# controller.net
KiCad netlist of a schematic drawn in EAGLE
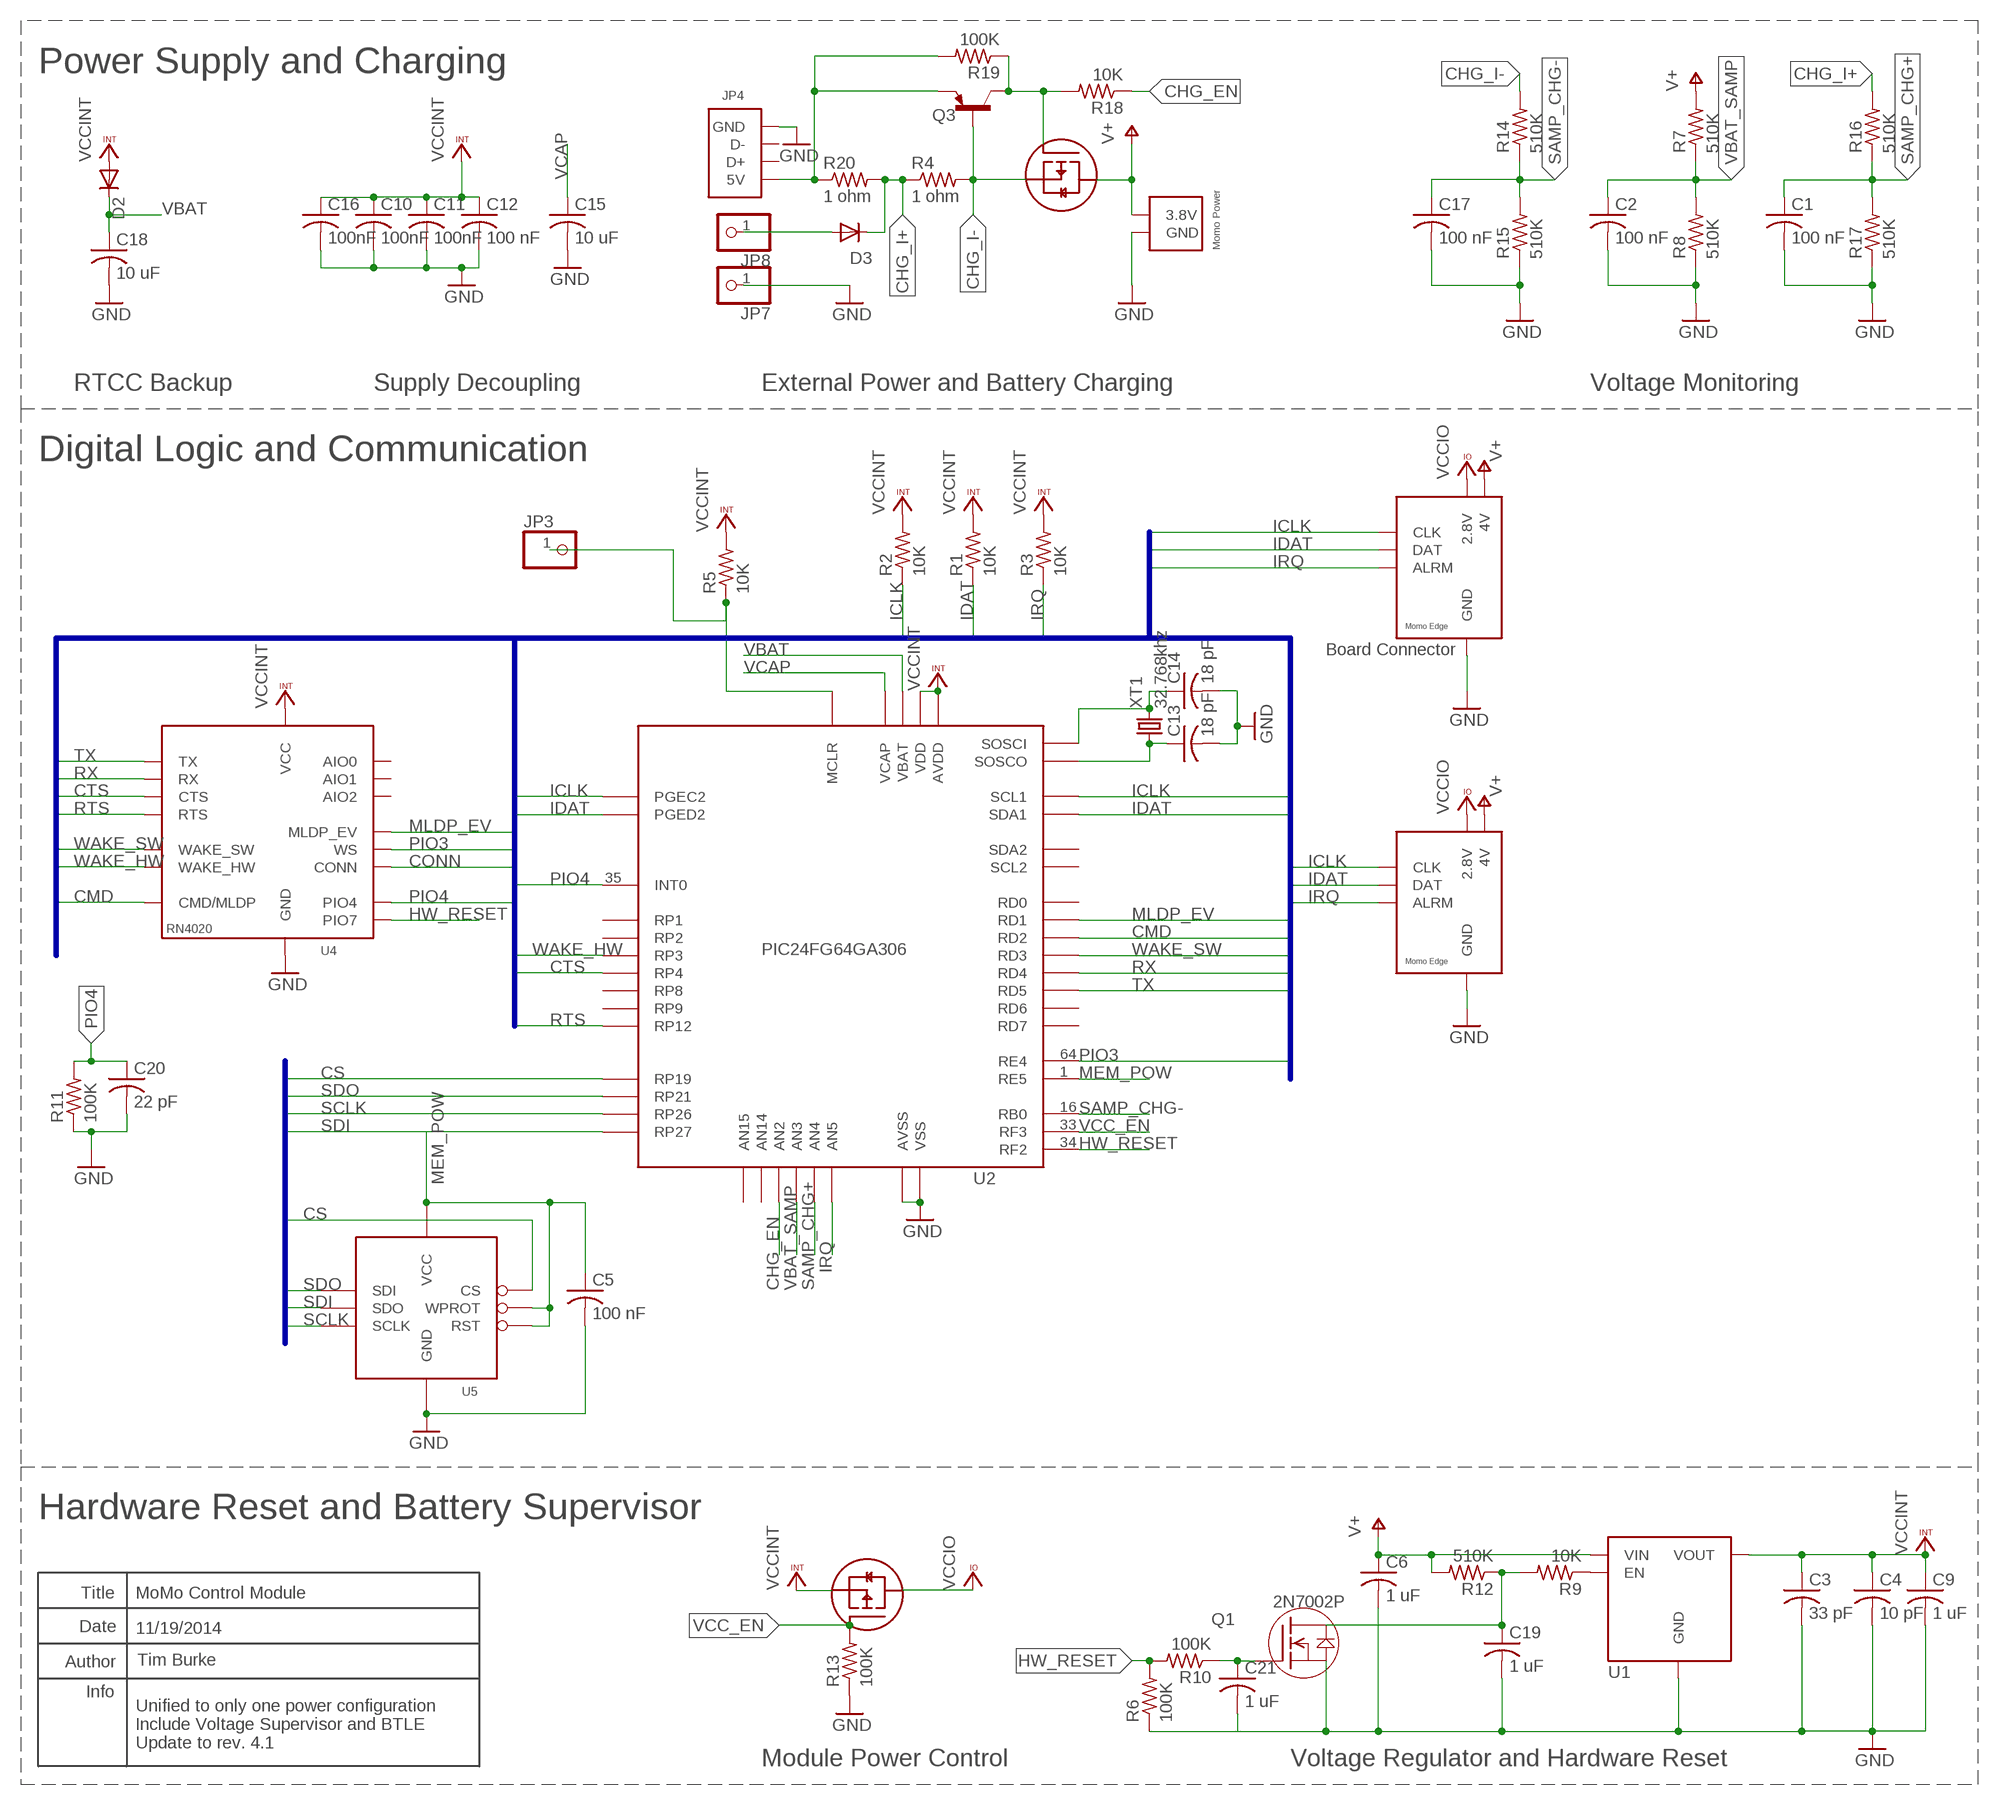
[diagram p0: schematic, sheet 1]

(export (version "E")
  (design (tool "Eeschema 10.0.6"))
  (components
    (comp (ref "C1")
      (value "100 nF")
      (footprint "eagle-import:C0402K")
      (libsource (lib "eagle-import") (part "C-USC0402K"))
    )
    (comp (ref "C2")
      (value "100 nF")
      (footprint "eagle-import:C0402K")
      (libsource (lib "eagle-import") (part "C-USC0402K"))
    )
    (comp (ref "C3")
      (value "33 pF")
      (footprint "eagle-import:C0402K")
      (libsource (lib "eagle-import") (part "C-USC0402K"))
    )
    (comp (ref "C4")
      (value "10 pF")
      (footprint "eagle-import:C0402K")
      (libsource (lib "eagle-import") (part "C-USC0402K"))
    )
    (comp (ref "C5")
      (value "100 nF")
      (footprint "eagle-import:C0402K")
      (libsource (lib "eagle-import") (part "C-USC0402K"))
    )
    (comp (ref "C6")
      (value "1 uF")
      (footprint "eagle-import:C0402K")
      (libsource (lib "eagle-import") (part "C-USC0402K"))
    )
    (comp (ref "C9")
      (value "1 uF")
      (footprint "eagle-import:C0402K")
      (libsource (lib "eagle-import") (part "C-USC0402K"))
    )
    (comp (ref "C10")
      (value "100nF")
      (footprint "eagle-import:C0402K")
      (libsource (lib "eagle-import") (part "C-USC0402K"))
    )
    (comp (ref "C11")
      (value "100nF")
      (footprint "eagle-import:C0402K")
      (libsource (lib "eagle-import") (part "C-USC0402K"))
    )
    (comp (ref "C12")
      (value "100 nF")
      (footprint "eagle-import:C0402K")
      (libsource (lib "eagle-import") (part "C-USC0402K"))
    )
    (comp (ref "C13")
      (value "18 pF")
      (footprint "eagle-import:C0402K")
      (libsource (lib "eagle-import") (part "C-USC0402K"))
    )
    (comp (ref "C14")
      (value "18 pF")
      (footprint "eagle-import:C0402K")
      (libsource (lib "eagle-import") (part "C-USC0402K"))
    )
    (comp (ref "C15")
      (value "10 uF")
      (footprint "eagle-import:C0805K")
      (libsource (lib "eagle-import") (part "C-USC0805K"))
    )
    (comp (ref "C16")
      (value "100nF")
      (footprint "eagle-import:C0402K")
      (libsource (lib "eagle-import") (part "C-USC0402K"))
    )
    (comp (ref "C17")
      (value "100 nF")
      (footprint "eagle-import:C0402K")
      (libsource (lib "eagle-import") (part "C-USC0402K"))
    )
    (comp (ref "C18")
      (value "10 uF")
      (footprint "eagle-import:C0805K")
      (libsource (lib "eagle-import") (part "C-USC0805K"))
    )
    (comp (ref "C19")
      (value "1 uF")
      (footprint "eagle-import:C0402K")
      (libsource (lib "eagle-import") (part "C-USC0402K"))
    )
    (comp (ref "C20")
      (value "22 pF")
      (footprint "eagle-import:C0402K")
      (libsource (lib "eagle-import") (part "C-USC0402K"))
    )
    (comp (ref "C21")
      (value "1 uF")
      (footprint "eagle-import:C0402K")
      (libsource (lib "eagle-import") (part "C-USC0402K"))
    )
    (comp (ref "D2")
      (value "DIODE-SC79_INFINEON")
      (footprint "eagle-import:SC79_INFINEON")
      (libsource (lib "eagle-import") (part "DIODE-SC79_INFINEON"))
    )
    (comp (ref "D3")
      (value "DIODE-SC79_INFINEON")
      (footprint "eagle-import:SC79_INFINEON")
      (libsource (lib "eagle-import") (part "DIODE-SC79_INFINEON"))
    )
    (comp (ref "JP1")
      (value "MOMO-VERT-6M")
      (footprint "eagle-import:1X06")
      (libsource (lib "eagle-import") (part "MOMO-VERT-6M"))
    )
    (comp (ref "JP2")
      (value "MOMO-EDGE-6F")
      (footprint "eagle-import:MOMO-EDGE-8F")
      (libsource (lib "eagle-import") (part "MOMO-EDGE-6F"))
    )
    (comp (ref "JP3")
      (value "PINHD-1X1")
      (footprint "eagle-import:1X01")
      (libsource (lib "eagle-import") (part "PINHD-1X1"))
    )
    (comp (ref "JP4")
      (value "CONN-MICROUSB-B-RCPT")
      (footprint "eagle-import:MICROUSB-B-FCI")
      (libsource (lib "eagle-import") (part "CONN-MICROUSB-B-RCPT"))
    )
    (comp (ref "JP5")
      (value "MOMO-PWR-HOUSED")
      (footprint "eagle-import:MOMO-PWR-HOUSED")
      (libsource (lib "eagle-import") (part "MOMO-PWR-HOUSED"))
    )
    (comp (ref "JP7")
      (value "PINHD-1X1")
      (footprint "eagle-import:1X01")
      (libsource (lib "eagle-import") (part "PINHD-1X1"))
    )
    (comp (ref "JP8")
      (value "PINHD-1X1")
      (footprint "eagle-import:1X01")
      (libsource (lib "eagle-import") (part "PINHD-1X1"))
    )
    (comp (ref "Q1")
      (value "MOSFET-N")
      (footprint "eagle-import:SOT-23")
      (description "N-Channel MOSFET 2N7002P")
      (fields (field (name "DIGIKEY-PN") "568-5818-1-ND"))
      (libsource (lib "eagle-import") (part "MOSFET-N"))
    )
    (comp (ref "Q2")
      (value "P-MOSFET")
      (footprint "eagle-import:SOT23")
      (description "P Channel MOSFET")
      (fields (field (name "DIGIKEY-PN") "IRLML6402PBFCT-ND"))
      (libsource (lib "eagle-import") (part "P-MOSFET"))
    )
    (comp (ref "Q3")
      (value "MMBTA56-SOT23")
      (footprint "eagle-import:SOT23")
      (description "PNP Transistor")
      (libsource (lib "eagle-import") (part "-?SOT23MMBTA56"))
    )
    (comp (ref "Q4")
      (value "P-MOSFET")
      (footprint "eagle-import:SOT23")
      (fields (field (name "DIGIKEY-PN") "IRLML6402PBFCT-ND"))
      (libsource (lib "eagle-import") (part "P-MOSFET"))
    )
    (comp (ref "R1")
      (value "10K")
      (footprint "eagle-import:R0603")
      (libsource (lib "eagle-import") (part "R-US_R0603"))
    )
    (comp (ref "R2")
      (value "10K")
      (footprint "eagle-import:R0603")
      (libsource (lib "eagle-import") (part "R-US_R0603"))
    )
    (comp (ref "R3")
      (value "10K")
      (footprint "eagle-import:R0603")
      (libsource (lib "eagle-import") (part "R-US_R0603"))
    )
    (comp (ref "R4")
      (value "1 ohm")
      (footprint "eagle-import:R1206")
      (libsource (lib "eagle-import") (part "R-US_R1206"))
    )
    (comp (ref "R5")
      (value "10K")
      (footprint "eagle-import:R0603")
      (libsource (lib "eagle-import") (part "R-US_R0603"))
    )
    (comp (ref "R6")
      (value "100K")
      (footprint "eagle-import:R0603")
      (libsource (lib "eagle-import") (part "R-US_R0603"))
    )
    (comp (ref "R7")
      (value "510K")
      (footprint "eagle-import:R0603")
      (libsource (lib "eagle-import") (part "R-US_R0603"))
    )
    (comp (ref "R8")
      (value "510K")
      (footprint "eagle-import:R0603")
      (libsource (lib "eagle-import") (part "R-US_R0603"))
    )
    (comp (ref "R9")
      (value "10K")
      (footprint "eagle-import:R0603")
      (libsource (lib "eagle-import") (part "R-US_R0603"))
    )
    (comp (ref "R10")
      (value "100K")
      (footprint "eagle-import:R0603")
      (libsource (lib "eagle-import") (part "R-US_R0603"))
    )
    (comp (ref "R11")
      (value "100K")
      (footprint "eagle-import:R0603")
      (libsource (lib "eagle-import") (part "R-US_R0603"))
    )
    (comp (ref "R12")
      (value "510K")
      (footprint "eagle-import:R0603")
      (libsource (lib "eagle-import") (part "R-US_R0603"))
    )
    (comp (ref "R13")
      (value "100K")
      (footprint "eagle-import:R0603")
      (libsource (lib "eagle-import") (part "R-US_R0603"))
    )
    (comp (ref "R14")
      (value "510K")
      (footprint "eagle-import:R0603")
      (libsource (lib "eagle-import") (part "R-US_R0603"))
    )
    (comp (ref "R15")
      (value "510K")
      (footprint "eagle-import:R0603")
      (libsource (lib "eagle-import") (part "R-US_R0603"))
    )
    (comp (ref "R16")
      (value "510K")
      (footprint "eagle-import:R0603")
      (libsource (lib "eagle-import") (part "R-US_R0603"))
    )
    (comp (ref "R17")
      (value "510K")
      (footprint "eagle-import:R0603")
      (libsource (lib "eagle-import") (part "R-US_R0603"))
    )
    (comp (ref "R18")
      (value "10K")
      (footprint "eagle-import:R0603")
      (libsource (lib "eagle-import") (part "R-US_R0603"))
    )
    (comp (ref "R19")
      (value "100K")
      (footprint "eagle-import:R0603")
      (libsource (lib "eagle-import") (part "R-US_R0603"))
    )
    (comp (ref "R20")
      (value "1 ohm")
      (footprint "eagle-import:R1206")
      (libsource (lib "eagle-import") (part "R-US_R1206"))
    )
    (comp (ref "U1")
      (value "XC6504-LINEAR-REGULATOR")
      (footprint "eagle-import:SOT23-5L")
      (libsource (lib "eagle-import") (part "XC6504-LINEAR-REGULATOR"))
    )
    (comp (ref "U2")
      (value "PIC24FJ64GA306")
      (footprint "eagle-import:TQFP64-10X10")
      (libsource (lib "eagle-import") (part "PIC24FJ64GA306"))
    )
    (comp (ref "U4")
      (value "RN4020_BT_4.0_MODULE")
      (footprint "eagle-import:RN20-BTLE-MODULE")
      (libsource (lib "eagle-import") (part "RN4020_BT_4.0_MODULE"))
    )
    (comp (ref "U5")
      (value "FLASH8MSOP8")
      (footprint "eagle-import:SOP08")
      (fields (field (name "DIGIKEY-PN") "M25PX80-VMN6TPCT-ND"))
      (libsource (lib "eagle-import") (part "FLASH8MSOP8"))
    )
    (comp (ref "XT1")
      (value "32.768khz")
      (footprint "eagle-import:TC26H")
      (libsource (lib "eagle-import") (part "XTAL-W-CAN-PAD"))
    )
  )
  (nets
    (net (code "1") (name "/CMD") (class "Default")
      (node (ref "U2") (pin "50") (pinfunction "RD2_50") (pintype "bidirectional"))
      (node (ref "U4") (pin "CMD/MLDP") (pinfunction "CMD/MLDP_CMD/MLDP") (pintype "bidirectional"))
    )
    (net (code "2") (name "/CONN") (class "Default")
      (node (ref "U4") (pin "PIO1") (pinfunction "CONN_PIO1") (pintype "bidirectional"))
    )
    (net (code "3") (name "/CS") (class "Default")
      (node (ref "U2") (pin "6") (pinfunction "RP19_6") (pintype "bidirectional"))
      (node (ref "U5") (pin "1") (pinfunction "CS_1") (pintype "bidirectional"))
    )
    (net (code "4") (name "/CTS") (class "Default")
      (node (ref "U2") (pin "43") (pinfunction "RP4_43") (pintype "bidirectional"))
      (node (ref "U4") (pin "PIO5") (pinfunction "CTS_PIO5") (pintype "bidirectional"))
    )
    (net (code "5") (name "/ICLK") (class "Default")
      (node (ref "JP1") (pin "3") (pinfunction "CLK_3") (pintype "bidirectional"))
      (node (ref "JP2") (pin "CLK") (pinfunction "CLK_CLK") (pintype "bidirectional"))
      (node (ref "R2") (pin "1") (pinfunction "1_1") (pintype "passive"))
      (node (ref "U2") (pin "17") (pinfunction "PGEC2_17") (pintype "bidirectional"))
      (node (ref "U2") (pin "37") (pinfunction "SCL1_37") (pintype "bidirectional"))
    )
    (net (code "6") (name "/IDAT") (class "Default")
      (node (ref "JP1") (pin "4") (pinfunction "DAT_4") (pintype "bidirectional"))
      (node (ref "JP2") (pin "DAT") (pinfunction "DAT_DAT") (pintype "bidirectional"))
      (node (ref "R1") (pin "1") (pinfunction "1_1") (pintype "passive"))
      (node (ref "U2") (pin "18") (pinfunction "PGED2_18") (pintype "bidirectional"))
      (node (ref "U2") (pin "36") (pinfunction "SDA1_36") (pintype "bidirectional"))
    )
    (net (code "7") (name "/IRQ") (class "Default")
      (node (ref "JP1") (pin "5") (pinfunction "ALRM_5") (pintype "bidirectional"))
      (node (ref "JP2") (pin "ARLM") (pinfunction "ALRM_ARLM") (pintype "bidirectional"))
      (node (ref "R3") (pin "1") (pinfunction "1_1") (pintype "passive"))
      (node (ref "U2") (pin "11") (pinfunction "AN5_11") (pintype "bidirectional"))
    )
    (net (code "8") (name "/MEM_POW") (class "Default")
      (node (ref "C5") (pin "1") (pinfunction "1_1") (pintype "passive"))
      (node (ref "U2") (pin "1") (pinfunction "RE5_1") (pintype "bidirectional"))
      (node (ref "U5") (pin "3") (pinfunction "WPROT_3") (pintype "bidirectional"))
      (node (ref "U5") (pin "7") (pinfunction "RST_7") (pintype "bidirectional"))
      (node (ref "U5") (pin "8") (pinfunction "VCC_8") (pintype "power_in"))
    )
    (net (code "9") (name "/MLDP_EV") (class "Default")
      (node (ref "U2") (pin "49") (pinfunction "RD1_49") (pintype "bidirectional"))
      (node (ref "U4") (pin "PIO2") (pinfunction "MLDP_EV_PIO2") (pintype "bidirectional"))
    )
    (net (code "10") (name "/PIO3") (class "Default")
      (node (ref "U2") (pin "64") (pinfunction "RE4_64") (pintype "bidirectional"))
      (node (ref "U4") (pin "PIO3") (pinfunction "WS_PIO3") (pintype "bidirectional"))
    )
    (net (code "11") (name "/RTS") (class "Default")
      (node (ref "U2") (pin "45") (pinfunction "RP12_45") (pintype "bidirectional"))
      (node (ref "U4") (pin "RTS/PIO6") (pinfunction "RTS_RTS/PIO6") (pintype "bidirectional"))
    )
    (net (code "12") (name "/RX") (class "Default")
      (node (ref "U2") (pin "52") (pinfunction "RD4_52") (pintype "bidirectional"))
      (node (ref "U4") (pin "UART_RX") (pinfunction "RX_UART_RX") (pintype "bidirectional"))
    )
    (net (code "13") (name "/SCLK") (class "Default")
      (node (ref "U2") (pin "5") (pinfunction "RP26_5") (pintype "bidirectional"))
      (node (ref "U5") (pin "6") (pinfunction "SCLK_6") (pintype "bidirectional"))
    )
    (net (code "14") (name "/SDI") (class "Default")
      (node (ref "U2") (pin "8") (pinfunction "RP27_8") (pintype "bidirectional"))
      (node (ref "U5") (pin "2") (pinfunction "SDO_2") (pintype "bidirectional"))
    )
    (net (code "15") (name "/SDO") (class "Default")
      (node (ref "U2") (pin "4") (pinfunction "RP21_4") (pintype "bidirectional"))
      (node (ref "U5") (pin "5") (pinfunction "SDI_5") (pintype "bidirectional"))
    )
    (net (code "16") (name "/TX") (class "Default")
      (node (ref "U2") (pin "53") (pinfunction "RD5_53") (pintype "bidirectional"))
      (node (ref "U4") (pin "UART_TX") (pinfunction "TX_UART_TX") (pintype "bidirectional"))
    )
    (net (code "17") (name "/VBAT") (class "Default")
      (node (ref "C18") (pin "1") (pinfunction "1_1") (pintype "passive"))
      (node (ref "D2") (pin "C") (pinfunction "C_C") (pintype "passive"))
      (node (ref "U2") (pin "57") (pinfunction "VBAT_57") (pintype "bidirectional"))
    )
    (net (code "18") (name "/VCAP") (class "Default")
      (node (ref "C15") (pin "1") (pinfunction "1_1") (pintype "passive"))
      (node (ref "U2") (pin "56") (pinfunction "VCAP_56") (pintype "bidirectional"))
    )
    (net (code "19") (name "/WAKE_HW") (class "Default")
      (node (ref "U2") (pin "44") (pinfunction "RP3_44") (pintype "bidirectional"))
      (node (ref "U4") (pin "WAKE_HW") (pinfunction "WAKE_HW_WAKE_HW") (pintype "bidirectional"))
    )
    (net (code "20") (name "/WAKE_SW") (class "Default")
      (node (ref "U2") (pin "51") (pinfunction "RD3_51") (pintype "bidirectional"))
      (node (ref "U4") (pin "WAKE_SW") (pinfunction "WAKE_SW_WAKE_SW") (pintype "bidirectional"))
    )
    (net (code "21") (name "CHG_EN") (class "Default")
      (node (ref "R18") (pin "1") (pinfunction "1_1") (pintype "passive"))
      (node (ref "U2") (pin "14") (pinfunction "AN2_14") (pintype "bidirectional"))
    )
    (net (code "22") (name "CHG_I+") (class "Default")
      (node (ref "D3") (pin "C") (pinfunction "C_C") (pintype "passive"))
      (node (ref "R16") (pin "2") (pinfunction "2_2") (pintype "passive"))
      (node (ref "R20") (pin "2") (pinfunction "2_2") (pintype "passive"))
      (node (ref "R4") (pin "1") (pinfunction "1_1") (pintype "passive"))
    )
    (net (code "23") (name "CHG_I-") (class "Default")
      (node (ref "Q3") (pin "1") (pinfunction "B_1") (pintype "passive"))
      (node (ref "Q4") (pin "2") (pinfunction "SOURCE_2") (pintype "bidirectional"))
      (node (ref "R14") (pin "2") (pinfunction "2_2") (pintype "passive"))
      (node (ref "R4") (pin "2") (pinfunction "2_2") (pintype "passive"))
    )
    (net (code "24") (name "GND") (class "Default")
      (node (ref "C1") (pin "2") (pinfunction "2_2") (pintype "passive"))
      (node (ref "C10") (pin "2") (pinfunction "2_2") (pintype "passive"))
      (node (ref "C11") (pin "2") (pinfunction "2_2") (pintype "passive"))
      (node (ref "C12") (pin "2") (pinfunction "2_2") (pintype "passive"))
      (node (ref "C13") (pin "2") (pinfunction "2_2") (pintype "passive"))
      (node (ref "C14") (pin "2") (pinfunction "2_2") (pintype "passive"))
      (node (ref "C15") (pin "2") (pinfunction "2_2") (pintype "passive"))
      (node (ref "C16") (pin "2") (pinfunction "2_2") (pintype "passive"))
      (node (ref "C17") (pin "2") (pinfunction "2_2") (pintype "passive"))
      (node (ref "C18") (pin "2") (pinfunction "2_2") (pintype "passive"))
      (node (ref "C19") (pin "2") (pinfunction "2_2") (pintype "passive"))
      (node (ref "C2") (pin "2") (pinfunction "2_2") (pintype "passive"))
      (node (ref "C20") (pin "2") (pinfunction "2_2") (pintype "passive"))
      (node (ref "C21") (pin "2") (pinfunction "2_2") (pintype "passive"))
      (node (ref "C3") (pin "2") (pinfunction "2_2") (pintype "passive"))
      (node (ref "C4") (pin "2") (pinfunction "2_2") (pintype "passive"))
      (node (ref "C5") (pin "2") (pinfunction "2_2") (pintype "passive"))
      (node (ref "C6") (pin "2") (pinfunction "2_2") (pintype "passive"))
      (node (ref "C9") (pin "2") (pinfunction "2_2") (pintype "passive"))
      (node (ref "JP1") (pin "7") (pinfunction "GND_7") (pintype "power_in"))
      (node (ref "JP2") (pin "GND") (pinfunction "GND_GND") (pintype "power_in"))
      (node (ref "JP4") (pin "5") (pinfunction "GND_5") (pintype "power_in"))
      (node (ref "JP4") (pin "GND2") (pinfunction "GND_GND2") (pintype "power_in"))
      (node (ref "JP4") (pin "GND3") (pinfunction "GND_GND3") (pintype "power_in"))
      (node (ref "JP4") (pin "GND4") (pinfunction "GND_GND4") (pintype "power_in"))
      (node (ref "JP4") (pin "GND5") (pinfunction "GND_GND5") (pintype "power_in"))
      (node (ref "JP4") (pin "GND6") (pinfunction "GND_GND6") (pintype "power_in"))
      (node (ref "JP5") (pin "2") (pinfunction "GND_2") (pintype "power_in"))
      (node (ref "JP7") (pin "1") (pinfunction "1_1") (pintype "passive"))
      (node (ref "Q1") (pin "2") (pinfunction "S_2") (pintype "passive"))
      (node (ref "R11") (pin "1") (pinfunction "1_1") (pintype "passive"))
      (node (ref "R13") (pin "1") (pinfunction "1_1") (pintype "passive"))
      (node (ref "R15") (pin "1") (pinfunction "1_1") (pintype "passive"))
      (node (ref "R17") (pin "1") (pinfunction "1_1") (pintype "passive"))
      (node (ref "R6") (pin "1") (pinfunction "1_1") (pintype "passive"))
      (node (ref "R8") (pin "1") (pinfunction "1_1") (pintype "passive"))
      (node (ref "U1") (pin "2") (pinfunction "GND_2") (pintype "power_in"))
      (node (ref "U2") (pin "20") (pinfunction "AVSS_20") (pintype "bidirectional"))
      (node (ref "U2") (pin "25") (pinfunction "VSS_25") (pintype "bidirectional"))
      (node (ref "U2") (pin "41") (pinfunction "VSS_41") (pintype "bidirectional"))
      (node (ref "U2") (pin "9") (pinfunction "VSS_9") (pintype "bidirectional"))
      (node (ref "U4") (pin "GND") (pinfunction "GND_GND") (pintype "bidirectional"))
      (node (ref "U4") (pin "GND1") (pinfunction "GND_GND1") (pintype "bidirectional"))
      (node (ref "U4") (pin "SHIELD1") (pinfunction "GND_SHIELD1") (pintype "bidirectional"))
      (node (ref "U4") (pin "SHIELD2") (pinfunction "GND_SHIELD2") (pintype "bidirectional"))
      (node (ref "U4") (pin "SHIELD3") (pinfunction "GND_SHIELD3") (pintype "bidirectional"))
      (node (ref "U4") (pin "SHIELD4") (pinfunction "GND_SHIELD4") (pintype "bidirectional"))
      (node (ref "U5") (pin "4") (pinfunction "GND_4") (pintype "power_in"))
    )
    (net (code "25") (name "HW_RESET") (class "Default")
      (node (ref "R10") (pin "2") (pinfunction "2_2") (pintype "passive"))
      (node (ref "R6") (pin "2") (pinfunction "2_2") (pintype "passive"))
      (node (ref "U2") (pin "34") (pinfunction "RF2_34") (pintype "bidirectional"))
      (node (ref "U4") (pin "PIO7") (pinfunction "PIO7_PIO7") (pintype "bidirectional"))
    )
    (net (code "26") (name "Net-(D3-PadA)") (class "Default")
      (node (ref "D3") (pin "A") (pinfunction "A_A") (pintype "passive"))
      (node (ref "JP8") (pin "1") (pinfunction "1_1") (pintype "passive"))
    )
    (net (code "27") (name "Net-(JP4-5V)") (class "Default")
      (node (ref "JP4") (pin "1") (pinfunction "5V_1") (pintype "power_in"))
      (node (ref "Q3") (pin "2") (pinfunction "E_2") (pintype "passive"))
      (node (ref "R19") (pin "2") (pinfunction "2_2") (pintype "passive"))
      (node (ref "R20") (pin "1") (pinfunction "1_1") (pintype "passive"))
    )
    (net (code "28") (name "Net-(Q1-D)") (class "Default")
      (node (ref "C19") (pin "1") (pinfunction "1_1") (pintype "passive"))
      (node (ref "Q1") (pin "3") (pinfunction "D_3") (pintype "passive"))
      (node (ref "R12") (pin "1") (pinfunction "1_1") (pintype "passive"))
      (node (ref "R9") (pin "2") (pinfunction "2_2") (pintype "passive"))
    )
    (net (code "29") (name "Net-(Q1-G)") (class "Default")
      (node (ref "C21") (pin "1") (pinfunction "1_1") (pintype "passive"))
      (node (ref "Q1") (pin "1") (pinfunction "G_1") (pintype "passive"))
      (node (ref "R10") (pin "1") (pinfunction "1_1") (pintype "passive"))
    )
    (net (code "30") (name "Net-(Q3-C)") (class "Default")
      (node (ref "Q3") (pin "3") (pinfunction "C_3") (pintype "passive"))
      (node (ref "Q4") (pin "1") (pinfunction "GATE_1") (pintype "bidirectional"))
      (node (ref "R18") (pin "2") (pinfunction "2_2") (pintype "passive"))
      (node (ref "R19") (pin "1") (pinfunction "1_1") (pintype "passive"))
    )
    (net (code "31") (name "Net-(U1-EN)") (class "Default")
      (node (ref "R9") (pin "1") (pinfunction "1_1") (pintype "passive"))
      (node (ref "U1") (pin "3") (pinfunction "EN_3") (pintype "bidirectional"))
    )
    (net (code "32") (name "Net-(U2-MCLR)") (class "Default")
      (node (ref "JP3") (pin "1") (pinfunction "1_1") (pintype "passive"))
      (node (ref "R5") (pin "1") (pinfunction "1_1") (pintype "passive"))
      (node (ref "U2") (pin "7") (pinfunction "MCLR_7") (pintype "bidirectional"))
    )
    (net (code "33") (name "Net-(U2-SOSCI)") (class "Default")
      (node (ref "C14") (pin "1") (pinfunction "1_1") (pintype "passive"))
      (node (ref "U2") (pin "47") (pinfunction "SOSCI_47") (pintype "bidirectional"))
      (node (ref "XT1") (pin "2") (pinfunction "2_2") (pintype "passive"))
    )
    (net (code "34") (name "Net-(U2-SOSCO)") (class "Default")
      (node (ref "C13") (pin "1") (pinfunction "1_1") (pintype "passive"))
      (node (ref "U2") (pin "48") (pinfunction "SOSCO_48") (pintype "bidirectional"))
      (node (ref "XT1") (pin "1") (pinfunction "1_1") (pintype "passive"))
    )
    (net (code "35") (name "PIO4") (class "Default")
      (node (ref "C20") (pin "1") (pinfunction "1_1") (pintype "passive"))
      (node (ref "R11") (pin "2") (pinfunction "2_2") (pintype "passive"))
      (node (ref "U2") (pin "35") (pinfunction "INT0_35") (pintype "bidirectional"))
      (node (ref "U4") (pin "PIO4") (pinfunction "PIO4_PIO4") (pintype "bidirectional"))
    )
    (net (code "36") (name "SAMP_CHG+") (class "Default")
      (node (ref "C1") (pin "1") (pinfunction "1_1") (pintype "passive"))
      (node (ref "R16") (pin "1") (pinfunction "1_1") (pintype "passive"))
      (node (ref "R17") (pin "2") (pinfunction "2_2") (pintype "passive"))
      (node (ref "U2") (pin "12") (pinfunction "AN4_12") (pintype "bidirectional"))
    )
    (net (code "37") (name "SAMP_CHG-") (class "Default")
      (node (ref "C17") (pin "1") (pinfunction "1_1") (pintype "passive"))
      (node (ref "R14") (pin "1") (pinfunction "1_1") (pintype "passive"))
      (node (ref "R15") (pin "2") (pinfunction "2_2") (pintype "passive"))
      (node (ref "U2") (pin "16") (pinfunction "RB0_16") (pintype "bidirectional"))
    )
    (net (code "38") (name "V+") (class "Default")
      (node (ref "C6") (pin "1") (pinfunction "1_1") (pintype "passive"))
      (node (ref "JP1") (pin "6") (pinfunction "4V_6") (pintype "power_in"))
      (node (ref "JP2") (pin "V4") (pinfunction "4V_V4") (pintype "power_in"))
      (node (ref "JP5") (pin "1") (pinfunction "3.8V_1") (pintype "power_in"))
      (node (ref "Q4") (pin "3") (pinfunction "DRAIN_3") (pintype "bidirectional"))
      (node (ref "R12") (pin "2") (pinfunction "2_2") (pintype "passive"))
      (node (ref "R7") (pin "2") (pinfunction "2_2") (pintype "passive"))
      (node (ref "U1") (pin "1") (pinfunction "VIN_1") (pintype "power_in"))
    )
    (net (code "39") (name "VBAT_SAMP") (class "Default")
      (node (ref "C2") (pin "1") (pinfunction "1_1") (pintype "passive"))
      (node (ref "R7") (pin "1") (pinfunction "1_1") (pintype "passive"))
      (node (ref "R8") (pin "2") (pinfunction "2_2") (pintype "passive"))
      (node (ref "U2") (pin "13") (pinfunction "AN3_13") (pintype "bidirectional"))
    )
    (net (code "40") (name "VCCINT") (class "Default")
      (node (ref "C10") (pin "1") (pinfunction "1_1") (pintype "passive"))
      (node (ref "C11") (pin "1") (pinfunction "1_1") (pintype "passive"))
      (node (ref "C12") (pin "1") (pinfunction "1_1") (pintype "passive"))
      (node (ref "C16") (pin "1") (pinfunction "1_1") (pintype "passive"))
      (node (ref "C3") (pin "1") (pinfunction "1_1") (pintype "passive"))
      (node (ref "C4") (pin "1") (pinfunction "1_1") (pintype "passive"))
      (node (ref "C9") (pin "1") (pinfunction "1_1") (pintype "passive"))
      (node (ref "D2") (pin "A") (pinfunction "A_A") (pintype "passive"))
      (node (ref "Q2") (pin "2") (pinfunction "SOURCE_2") (pintype "bidirectional"))
      (node (ref "R1") (pin "2") (pinfunction "2_2") (pintype "passive"))
      (node (ref "R2") (pin "2") (pinfunction "2_2") (pintype "passive"))
      (node (ref "R3") (pin "2") (pinfunction "2_2") (pintype "passive"))
      (node (ref "R5") (pin "2") (pinfunction "2_2") (pintype "passive"))
      (node (ref "U1") (pin "5") (pinfunction "VOUT_5") (pintype "power_in"))
      (node (ref "U2") (pin "10") (pinfunction "VDD_10") (pintype "bidirectional"))
      (node (ref "U2") (pin "19") (pinfunction "AVDD_19") (pintype "bidirectional"))
      (node (ref "U2") (pin "26") (pinfunction "VDD_26") (pintype "bidirectional"))
      (node (ref "U2") (pin "38") (pinfunction "VDD_38") (pintype "bidirectional"))
      (node (ref "U4") (pin "VDD") (pinfunction "VCC_VDD") (pintype "bidirectional"))
    )
    (net (code "41") (name "VCCIO") (class "Default")
      (node (ref "JP1") (pin "1") (pinfunction "2.8V_1") (pintype "power_in"))
      (node (ref "JP2") (pin "V28") (pinfunction "2.8V_V28") (pintype "power_in"))
      (node (ref "Q2") (pin "3") (pinfunction "DRAIN_3") (pintype "bidirectional"))
    )
    (net (code "42") (name "VCC_EN") (class "Default")
      (node (ref "Q2") (pin "1") (pinfunction "GATE_1") (pintype "bidirectional"))
      (node (ref "R13") (pin "2") (pinfunction "2_2") (pintype "passive"))
      (node (ref "U2") (pin "33") (pinfunction "RF3_33") (pintype "bidirectional"))
    )
    (net (code "43") (name "unconnected-(JP4-D+-Pad3)") (class "Default")
      (node (ref "JP4") (pin "3") (pinfunction "D+_3") (pintype "bidirectional"))
    )
    (net (code "44") (name "unconnected-(JP4-D--Pad2)") (class "Default")
      (node (ref "JP4") (pin "2") (pinfunction "D-_2") (pintype "bidirectional"))
    )
    (net (code "45") (name "unconnected-(U2-AN14-Pad29)") (class "Default")
      (node (ref "U2") (pin "29") (pinfunction "AN14_29") (pintype "bidirectional"))
    )
    (net (code "46") (name "unconnected-(U2-AN15-Pad30)") (class "Default")
      (node (ref "U2") (pin "30") (pinfunction "AN15_30") (pintype "bidirectional"))
    )
    (net (code "47") (name "unconnected-(U2-RD0-Pad46)") (class "Default")
      (node (ref "U2") (pin "46") (pinfunction "RD0_46") (pintype "bidirectional"))
    )
    (net (code "48") (name "unconnected-(U2-RD6-Pad54)") (class "Default")
      (node (ref "U2") (pin "54") (pinfunction "RD6_54") (pintype "bidirectional"))
    )
    (net (code "49") (name "unconnected-(U2-RD7-Pad55)") (class "Default")
      (node (ref "U2") (pin "55") (pinfunction "RD7_55") (pintype "bidirectional"))
    )
    (net (code "50") (name "unconnected-(U2-RP1-Pad15)") (class "Default")
      (node (ref "U2") (pin "15") (pinfunction "RP1_15") (pintype "bidirectional"))
    )
    (net (code "51") (name "unconnected-(U2-RP2-Pad42)") (class "Default")
      (node (ref "U2") (pin "42") (pinfunction "RP2_42") (pintype "bidirectional"))
    )
    (net (code "52") (name "unconnected-(U2-RP8-Pad21)") (class "Default")
      (node (ref "U2") (pin "21") (pinfunction "RP8_21") (pintype "bidirectional"))
    )
    (net (code "53") (name "unconnected-(U2-RP9-Pad22)") (class "Default")
      (node (ref "U2") (pin "22") (pinfunction "RP9_22") (pintype "bidirectional"))
    )
    (net (code "54") (name "unconnected-(U2-SCL2-Pad32)") (class "Default")
      (node (ref "U2") (pin "32") (pinfunction "SCL2_32") (pintype "bidirectional"))
    )
    (net (code "55") (name "unconnected-(U2-SDA2-Pad31)") (class "Default")
      (node (ref "U2") (pin "31") (pinfunction "SDA2_31") (pintype "bidirectional"))
    )
    (net (code "56") (name "unconnected-(U4-PadAIO0)") (class "Default")
      (node (ref "U4") (pin "AIO0") (pinfunction "AIO0_AIO0") (pintype "bidirectional"))
    )
    (net (code "57") (name "unconnected-(U4-PadAIO1)") (class "Default")
      (node (ref "U4") (pin "AIO1") (pinfunction "AIO1_AIO1") (pintype "bidirectional"))
    )
    (net (code "58") (name "unconnected-(U4-PadAIO2)") (class "Default")
      (node (ref "U4") (pin "AIO2") (pinfunction "AIO2_AIO2") (pintype "bidirectional"))
    )
  )
)
